# Drive.net
KiCad netlist of a schematic drawn in Altium Designer
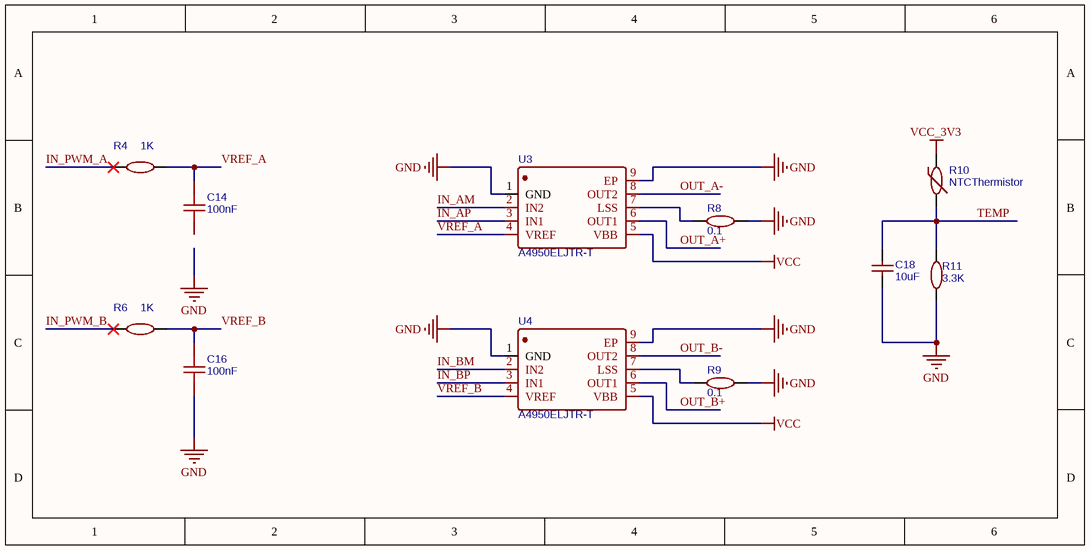
[diagram p0: Drive.SchDoc]

(export (version "E")
  (design (tool "Eeschema 10.0.6"))
  (components
    (comp (ref "C14")
      (value "100nF")
      (footprint "C0603")
      (fields
        (field (name "BOM_MANUFACTURER PART") "CL10B104KB8NNNC")
        (field (name "BOM_SUPPLIER PART") "C1591")
      )
      (libsource (lib "0.1uF") (part "100nF"))
    )
    (comp (ref "C16")
      (value "100nF")
      (footprint "C0603")
      (fields
        (field (name "BOM_MANUFACTURER PART") "CL10B104KB8NNNC")
        (field (name "BOM_SUPPLIER PART") "C1591")
      )
      (libsource (lib "0.1uF") (part "100nF"))
    )
    (comp (ref "C18")
      (value "10uF")
      (footprint "C1206")
      (fields
        (field (name "BOM_MANUFACTURER PART") "CL31A106KBHNNNE")
        (field (name "BOM_SUPPLIER PART") "C13585")
      )
      (libsource (lib "10uF") (part "10uF"))
    )
    (comp (ref "R4")
      (value "1K")
      (footprint "R0603")
      (fields
        (field (name "BOM_MANUFACTURER PART") "0603WAF1001T5E")
        (field (name "BOM_SUPPLIER PART") "C21190")
      )
      (libsource (lib "1K") (part "1K"))
    )
    (comp (ref "R6")
      (value "1K")
      (footprint "R0603")
      (fields
        (field (name "BOM_MANUFACTURER PART") "0603WAF1001T5E")
        (field (name "BOM_SUPPLIER PART") "C21190")
      )
      (libsource (lib "1K") (part "1K"))
    )
    (comp (ref "R8")
      (value "0.1")
      (footprint "R1206")
      (fields
        (field (name "BOM_MANUFACTURER PART") "1206W4F100LT5E")
        (field (name "BOM_SUPPLIER PART") "C25334")
      )
      (libsource (lib "0.1R") (part "0.1"))
    )
    (comp (ref "R9")
      (value "0.1")
      (footprint "R1206")
      (fields
        (field (name "BOM_MANUFACTURER PART") "1206W4F100LT5E")
        (field (name "BOM_SUPPLIER PART") "C25334")
      )
      (libsource (lib "0.1R") (part "0.1"))
    )
    (comp (ref "R10")
      (value "NTCThermistor")
      (footprint "R0402")
      (fields
        (field (name "BOM_MANUFACTURER PART") "NCP15XH103F03RC")
        (field (name "BOM_SUPPLIER PART") "C77131")
      )
      (libsource (lib "10K THERMISTOR") (part "NTCThermistor"))
    )
    (comp (ref "R11")
      (value "3.3K")
      (footprint "R0603_NEW")
      (fields
        (field (name "BOM_MANUFACTURER PART") "0603WAF3301T5E")
        (field (name "BOM_SUPPLIER PART") "C22978")
      )
      (libsource (lib "3.3K") (part "3.3K"))
    )
    (comp (ref "U3")
      (value "A4950ELJTR-T")
      (footprint "SOIC-8_L4.9-W3.9-P1.27-LS6.0-BL-EP")
      (fields (field (name "BOM_SUPPLIER PART") "C82404"))
      (libsource (lib "A4950") (part "A4950ELJTR-T"))
    )
    (comp (ref "U4")
      (value "A4950ELJTR-T")
      (footprint "SOIC-8_L4.9-W3.9-P1.27-LS6.0-BL-EP")
      (fields (field (name "BOM_SUPPLIER PART") "C82404"))
      (libsource (lib "A4950") (part "A4950ELJTR-T"))
    )
  )
  (nets
    (net (code "1") (name "/IN_AM") (class "Default")
      (node (ref "U3") (pin "2") (pinfunction "IN2_2") (pintype "passive"))
    )
    (net (code "2") (name "/IN_AP") (class "Default")
      (node (ref "U3") (pin "3") (pinfunction "IN1_3") (pintype "passive"))
    )
    (net (code "3") (name "/IN_BM") (class "Default")
      (node (ref "U4") (pin "2") (pinfunction "IN2_2") (pintype "passive"))
    )
    (net (code "4") (name "/IN_BP") (class "Default")
      (node (ref "U4") (pin "3") (pinfunction "IN1_3") (pintype "passive"))
    )
    (net (code "5") (name "/IN_PWM_A") (class "Default")
      (node (ref "R4") (pin "1") (pinfunction "1_1") (pintype "passive+no_connect"))
    )
    (net (code "6") (name "/IN_PWM_B") (class "Default")
      (node (ref "R6") (pin "1") (pinfunction "1_1") (pintype "passive+no_connect"))
    )
    (net (code "7") (name "/OUT_A+") (class "Default")
      (node (ref "U3") (pin "6") (pinfunction "OUT1_6") (pintype "passive"))
    )
    (net (code "8") (name "/OUT_A-") (class "Default")
      (node (ref "U3") (pin "8") (pinfunction "OUT2_8") (pintype "passive"))
    )
    (net (code "9") (name "/OUT_B+") (class "Default")
      (node (ref "U4") (pin "6") (pinfunction "OUT1_6") (pintype "passive"))
    )
    (net (code "10") (name "/OUT_B-") (class "Default")
      (node (ref "U4") (pin "8") (pinfunction "OUT2_8") (pintype "passive"))
    )
    (net (code "11") (name "/TEMP") (class "Default")
      (node (ref "C18") (pin "2") (pinfunction "2_2") (pintype "passive"))
      (node (ref "R10") (pin "2") (pinfunction "2_2") (pintype "passive"))
      (node (ref "R11") (pin "2") (pinfunction "2_2") (pintype "passive"))
    )
    (net (code "12") (name "/VREF_A") (class "Default")
      (node (ref "C14") (pin "2") (pinfunction "2_2") (pintype "passive"))
      (node (ref "R4") (pin "2") (pinfunction "2_2") (pintype "passive"))
      (node (ref "U3") (pin "4") (pinfunction "VREF_4") (pintype "passive"))
    )
    (net (code "13") (name "/VREF_B") (class "Default")
      (node (ref "C16") (pin "2") (pinfunction "2_2") (pintype "passive"))
      (node (ref "R6") (pin "2") (pinfunction "2_2") (pintype "passive"))
      (node (ref "U4") (pin "4") (pinfunction "VREF_4") (pintype "passive"))
    )
    (net (code "14") (name "GND") (class "Default")
      (node (ref "C16") (pin "1") (pinfunction "1_1") (pintype "passive"))
      (node (ref "C18") (pin "1") (pinfunction "1_1") (pintype "passive"))
      (node (ref "R11") (pin "1") (pinfunction "1_1") (pintype "passive"))
      (node (ref "R8") (pin "2") (pinfunction "2_2") (pintype "passive"))
      (node (ref "R9") (pin "2") (pinfunction "2_2") (pintype "passive"))
      (node (ref "U3") (pin "1") (pinfunction "GND_1") (pintype "passive"))
      (node (ref "U3") (pin "9") (pinfunction "EP_9") (pintype "passive"))
      (node (ref "U4") (pin "1") (pinfunction "GND_1") (pintype "passive"))
      (node (ref "U4") (pin "9") (pinfunction "EP_9") (pintype "passive"))
    )
    (net (code "15") (name "Net-(U3-LSS)") (class "Default")
      (node (ref "R8") (pin "1") (pinfunction "1_1") (pintype "passive"))
      (node (ref "U3") (pin "7") (pinfunction "LSS_7") (pintype "passive"))
    )
    (net (code "16") (name "Net-(U4-LSS)") (class "Default")
      (node (ref "R9") (pin "1") (pinfunction "1_1") (pintype "passive"))
      (node (ref "U4") (pin "7") (pinfunction "LSS_7") (pintype "passive"))
    )
    (net (code "17") (name "VCC") (class "Default")
      (node (ref "U3") (pin "5") (pinfunction "VBB_5") (pintype "passive"))
      (node (ref "U4") (pin "5") (pinfunction "VBB_5") (pintype "passive"))
    )
    (net (code "18") (name "VCC_3V3") (class "Default")
      (node (ref "R10") (pin "1") (pinfunction "1_1") (pintype "passive"))
    )
    (net (code "19") (name "unconnected-(C14-Pad1)") (class "Default")
      (node (ref "C14") (pin "1") (pinfunction "1_1") (pintype "passive"))
    )
  )
)
